# compact.net
KiCad netlist of a schematic drawn in EAGLE
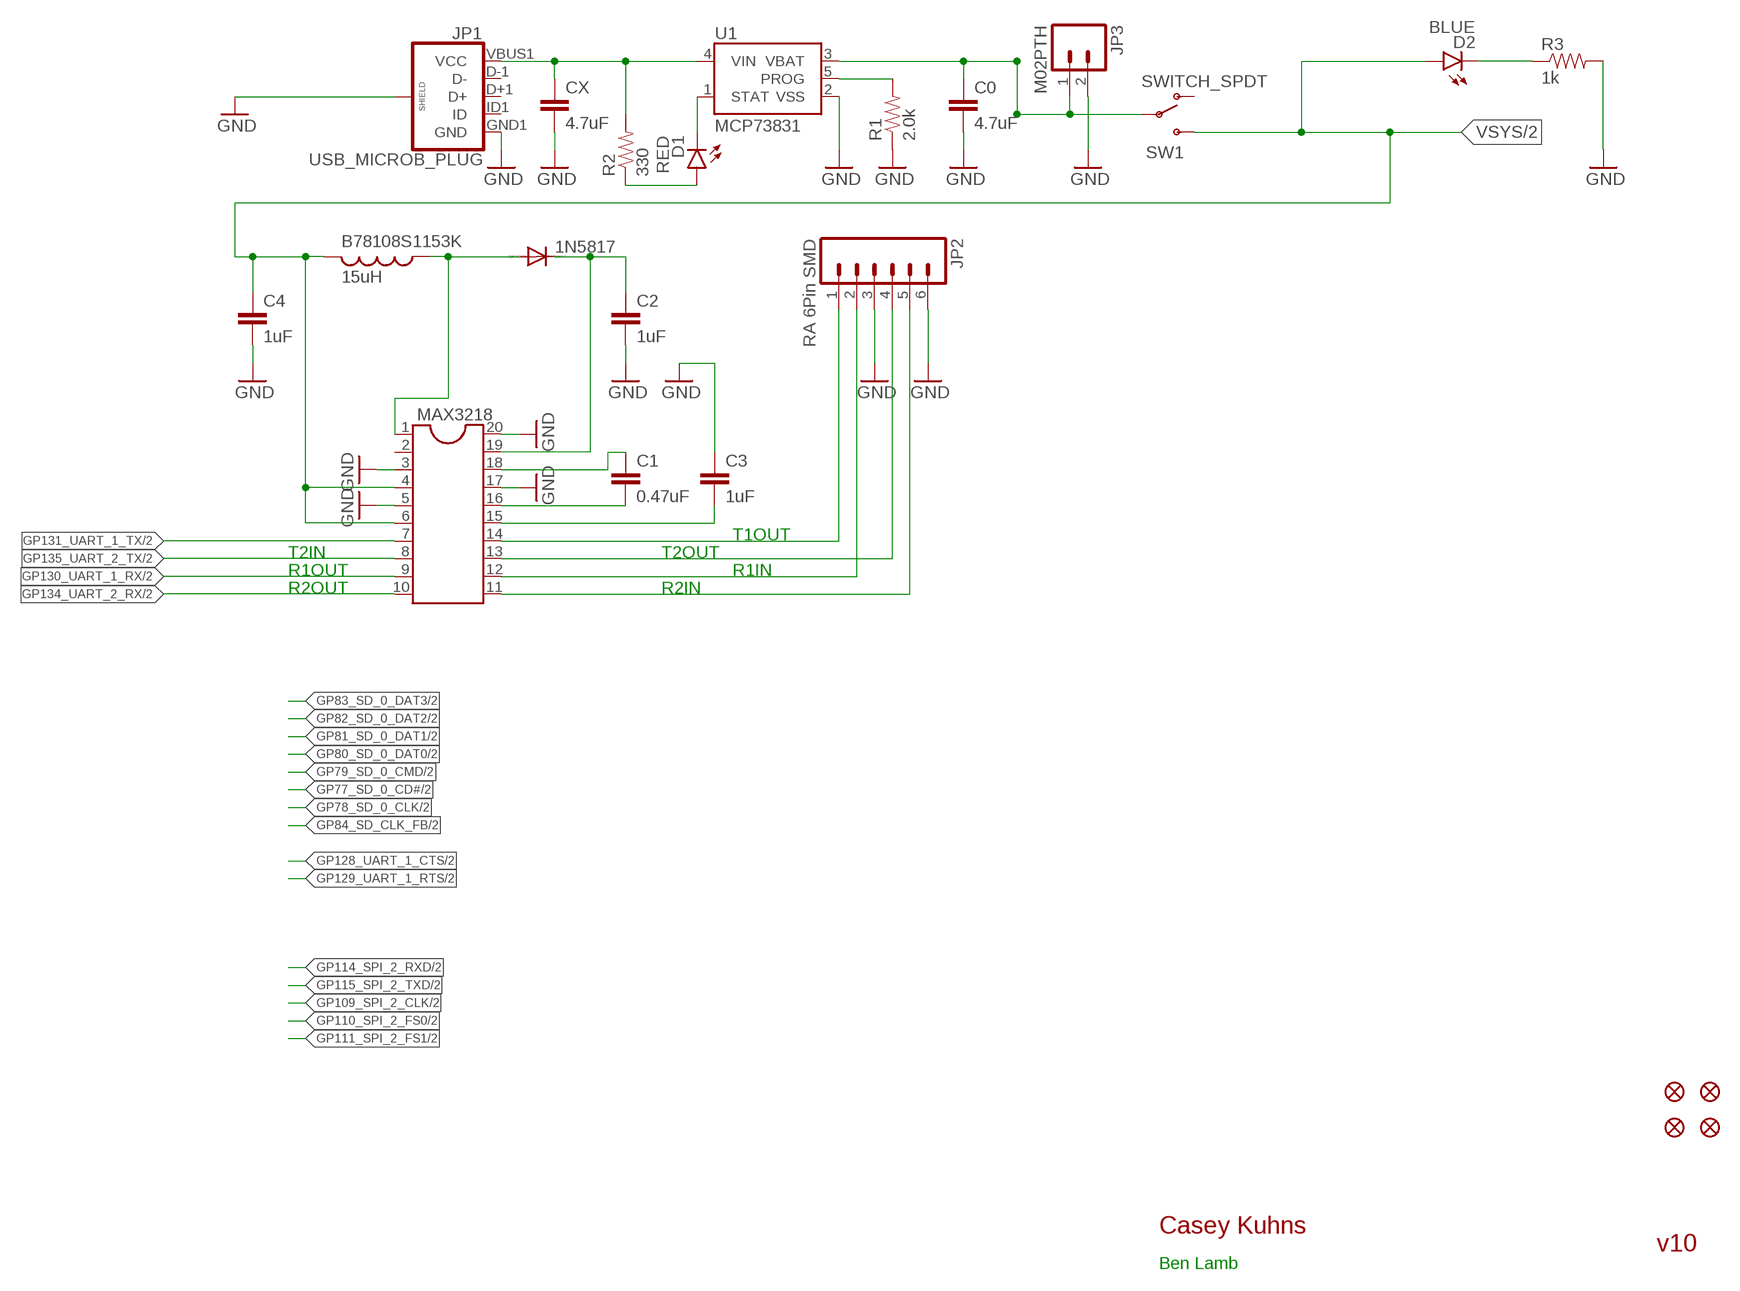
[diagram p0: schematic, sheet 1]
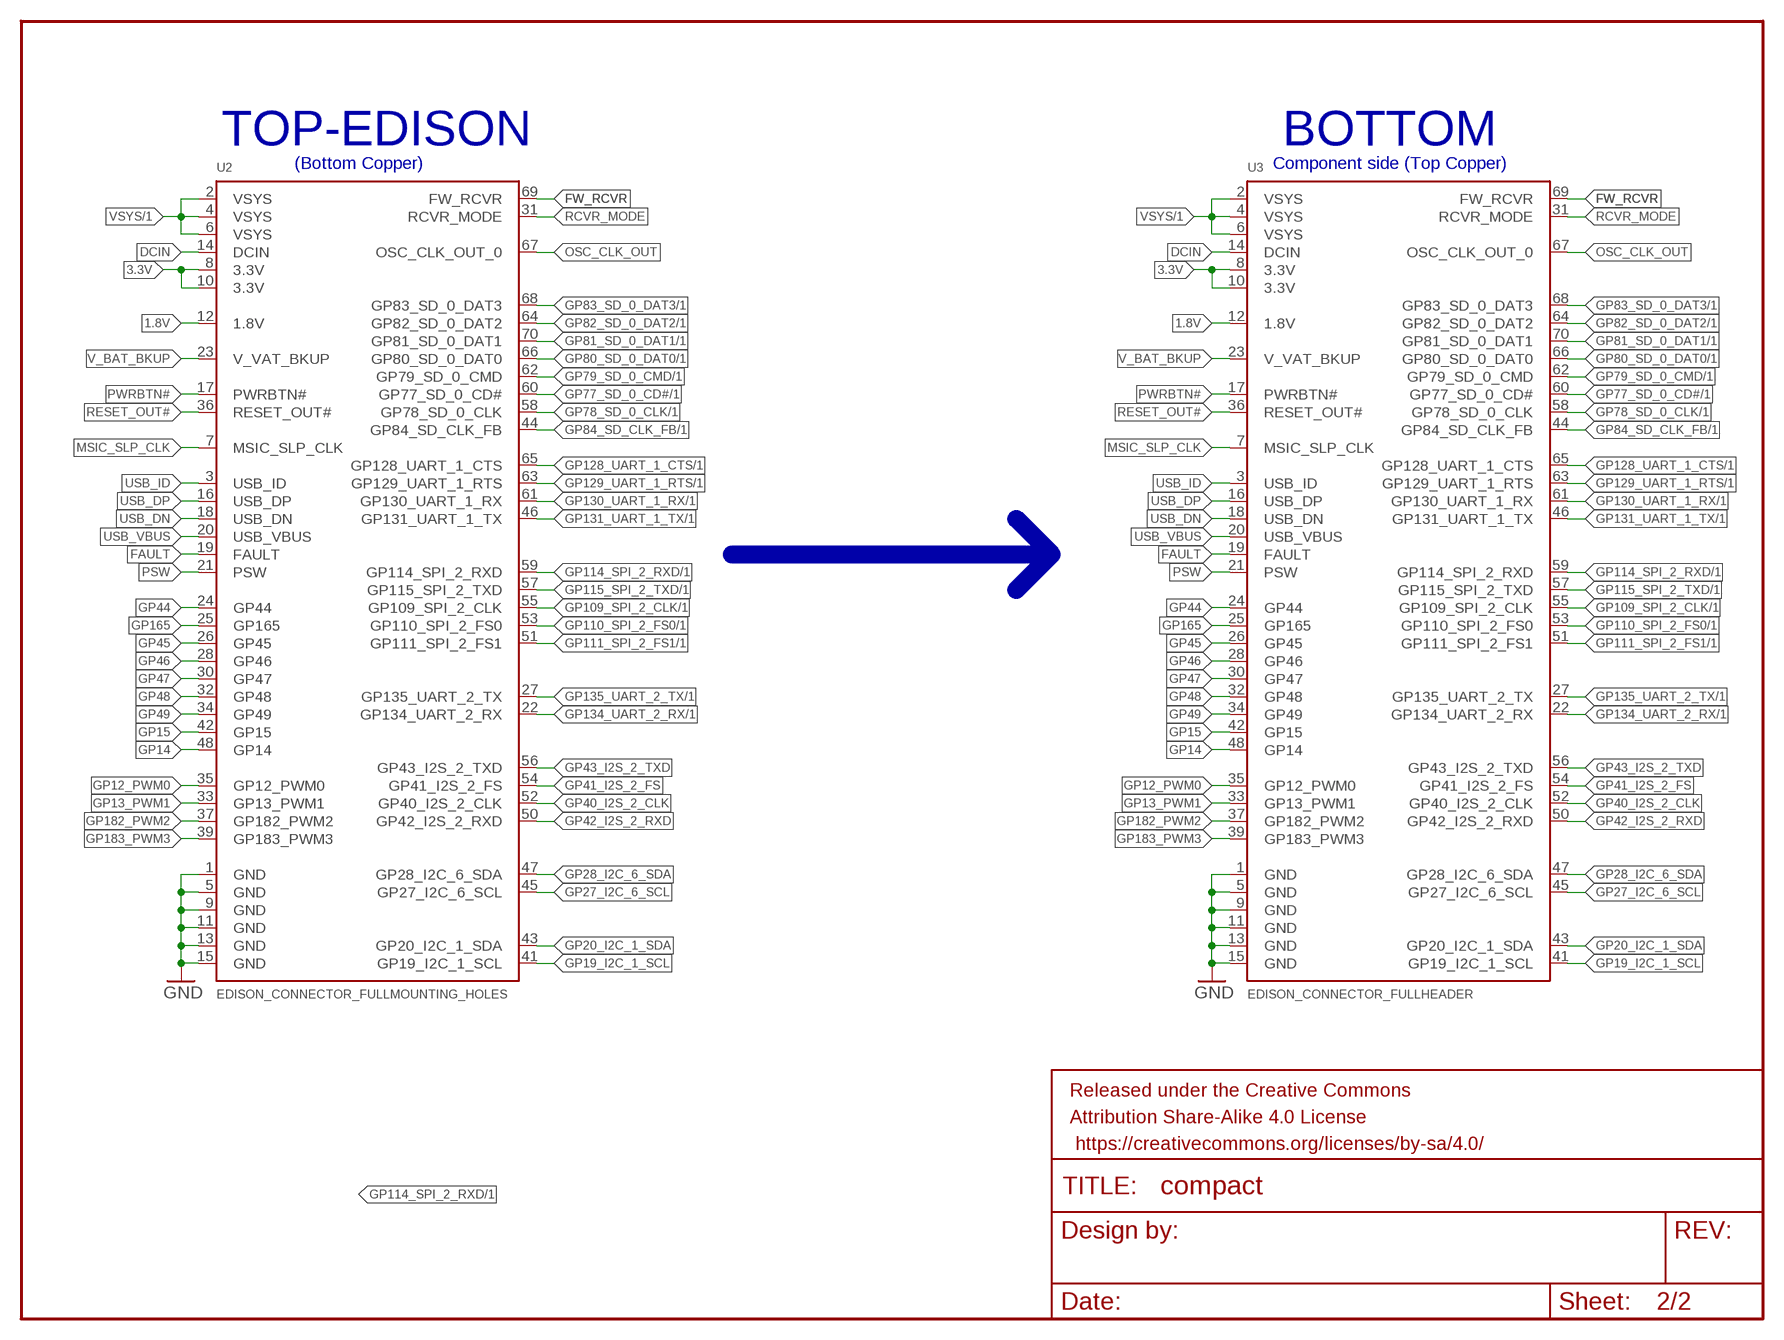
[diagram p1: schematic, sheet 2]

(export (version "E")
  (design (tool "Eeschema 10.0.6"))
  (components
    (comp (ref "FRAME2")
      (value "FRAME-LETTER")
      (footprint "eagle-import:CREATIVE_COMMONS")
      (libsource (lib "eagle-import") (part "FRAME-LETTER"))
    )
    (comp (ref "U2")
      (value "EDISON_CONNECTOR_FULLMOUNTING_HOLES")
      (footprint "eagle-import:EDISON_DAUGHTER")
      (libsource (lib "eagle-import") (part "EDISON_CONNECTOR_FULLMOUNTING_HOLES"))
    )
    (comp (ref "U3")
      (value "EDISON_CONNECTOR_FULLHEADER")
      (footprint "eagle-import:DF40C-70DP-0.4(51)")
      (libsource (lib "eagle-import") (part "EDISON_CONNECTOR_FULLHEADER"))
    )
    (comp (ref "1N5817")
      (value "DIODE-DO41-10")
      (footprint "eagle-import:DO41-10")
      (libsource (lib "eagle-import") (part "DIODE-DO41-10"))
    )
    (comp (ref "B78108S1153K")
      (value "15uH")
      (footprint "eagle-import:0207_15")
      (libsource (lib "eagle-import") (part "L-US0207/15"))
    )
    (comp (ref "C0")
      (value "4.7uF")
      (footprint "eagle-import:0603-CAP")
      (libsource (lib "eagle-import") (part "4.7UF-6.3V-10%(0603)0603"))
    )
    (comp (ref "C1")
      (value "0.47uF")
      (footprint "eagle-import:CAP-PTH-5MM")
      (libsource (lib "eagle-import") (part "CAPPTH1"))
    )
    (comp (ref "C2")
      (value "1uF")
      (footprint "eagle-import:CAP-PTH-5MM")
      (libsource (lib "eagle-import") (part "CAPPTH1"))
    )
    (comp (ref "C3")
      (value "1uF")
      (footprint "eagle-import:CAP-PTH-5MM")
      (libsource (lib "eagle-import") (part "CAPPTH1"))
    )
    (comp (ref "C4")
      (value "1uF")
      (footprint "eagle-import:CAP-PTH-5MM")
      (libsource (lib "eagle-import") (part "CAPPTH1"))
    )
    (comp (ref "CX")
      (value "4.7uF")
      (footprint "eagle-import:0603-CAP")
      (libsource (lib "eagle-import") (part "4.7UF-6.3V-10%(0603)0603"))
    )
    (comp (ref "D1")
      (value "RED")
      (footprint "eagle-import:LED-0603")
      (libsource (lib "eagle-import") (part "LED-RED0603"))
    )
    (comp (ref "D2")
      (value "BLUE")
      (footprint "eagle-import:LED-0603")
      (libsource (lib "eagle-import") (part "LED-BLUE0603"))
    )
    (comp (ref "FID1")
      (value "FIDUCIAL1X2")
      (footprint "eagle-import:FIDUCIAL-1X2")
      (libsource (lib "eagle-import") (part "FIDUCIAL1X2"))
    )
    (comp (ref "FID2")
      (value "FIDUCIAL1X2")
      (footprint "eagle-import:FIDUCIAL-1X2")
      (libsource (lib "eagle-import") (part "FIDUCIAL1X2"))
    )
    (comp (ref "FID3")
      (value "FIDUCIAL1X2")
      (footprint "eagle-import:FIDUCIAL-1X2")
      (libsource (lib "eagle-import") (part "FIDUCIAL1X2"))
    )
    (comp (ref "FID4")
      (value "FIDUCIAL1X2")
      (footprint "eagle-import:FIDUCIAL-1X2")
      (libsource (lib "eagle-import") (part "FIDUCIAL1X2"))
    )
    (comp (ref "JP1")
      (value "USB_MICROB_PLUG")
      (footprint "eagle-import:USB-B-MICRO-SMD_V03")
      (libsource (lib "eagle-import") (part "USB_MICROB_PLUGCONN-11752"))
    )
    (comp (ref "JP2")
      (value "RA 6Pin SMD")
      (footprint "eagle-import:1X06-SMD")
      (libsource (lib "eagle-import") (part "M06SMD"))
    )
    (comp (ref "JP3")
      (value "M02PTH")
      (footprint "eagle-import:1X02")
      (libsource (lib "eagle-import") (part "M02PTH"))
    )
    (comp (ref "MAX3218")
      (value "DIL20")
      (footprint "eagle-import:DIL20")
      (libsource (lib "eagle-import") (part "DIL20"))
    )
    (comp (ref "R1")
      (value "2.0k")
      (footprint "eagle-import:0603-RES")
      (libsource (lib "eagle-import") (part "2.0KOHM1/10W5%(0603)"))
    )
    (comp (ref "R2")
      (value "330")
      (footprint "eagle-import:0603-RES")
      (libsource (lib "eagle-import") (part "330OHM1/10W1%(0603)"))
    )
    (comp (ref "R3")
      (value "1k")
      (footprint "eagle-import:0603-RES")
      (libsource (lib "eagle-import") (part "1KOHM1/10W1%(0603)"))
    )
    (comp (ref "SW1")
      (value "SWITCH_SPDT")
      (footprint "eagle-import:KPS-1290")
      (libsource (lib "eagle-import") (part "SWITCH_SPDT"))
    )
    (comp (ref "U1")
      (value "MCP73831")
      (footprint "eagle-import:SOT23-5")
      (libsource (lib "eagle-import") (part "MCP73831"))
    )
  )
  (nets
    (net (code "1") (name "1.8V") (class "Default")
      (node (ref "U2") (pin "12") (pinfunction "1.8V_12") (pintype "bidirectional"))
      (node (ref "U3") (pin "12") (pinfunction "1.8V_12") (pintype "bidirectional"))
    )
    (net (code "2") (name "3.3V") (class "Default")
      (node (ref "U2") (pin "10") (pinfunction "3.3V_10") (pintype "bidirectional"))
      (node (ref "U2") (pin "8") (pinfunction "3.3V_8") (pintype "bidirectional"))
      (node (ref "U3") (pin "10") (pinfunction "3.3V_10") (pintype "bidirectional"))
      (node (ref "U3") (pin "8") (pinfunction "3.3V_8") (pintype "bidirectional"))
    )
    (net (code "3") (name "DCIN") (class "Default")
      (node (ref "U2") (pin "14") (pinfunction "DCIN_14") (pintype "bidirectional"))
      (node (ref "U3") (pin "14") (pinfunction "DCIN_14") (pintype "bidirectional"))
    )
    (net (code "4") (name "FAULT") (class "Default")
      (node (ref "U2") (pin "19") (pinfunction "FAULT_19") (pintype "bidirectional"))
      (node (ref "U3") (pin "19") (pinfunction "FAULT_19") (pintype "bidirectional"))
    )
    (net (code "5") (name "FW_RCVR") (class "Default")
      (node (ref "U2") (pin "69") (pinfunction "FW_RCVR_69") (pintype "bidirectional"))
      (node (ref "U3") (pin "69") (pinfunction "FW_RCVR_69") (pintype "bidirectional"))
    )
    (net (code "6") (name "GND") (class "Default")
      (node (ref "C0") (pin "2") (pinfunction "2_2") (pintype "passive"))
      (node (ref "C2") (pin "2") (pinfunction "2_2") (pintype "passive"))
      (node (ref "C3") (pin "1") (pinfunction "1_1") (pintype "passive"))
      (node (ref "C4") (pin "2") (pinfunction "2_2") (pintype "passive"))
      (node (ref "CX") (pin "2") (pinfunction "2_2") (pintype "passive"))
      (node (ref "JP1") (pin "GND1") (pinfunction "GND_GND1") (pintype "bidirectional"))
      (node (ref "JP1") (pin "SHIELD1") (pinfunction "SHIELD_SHIELD1") (pintype "bidirectional"))
      (node (ref "JP1") (pin "SHIELD2") (pinfunction "SHIELD_SHIELD2") (pintype "bidirectional"))
      (node (ref "JP1") (pin "SHIELD3") (pinfunction "SHIELD_SHIELD3") (pintype "bidirectional"))
      (node (ref "JP2") (pin "3") (pinfunction "3_3") (pintype "passive"))
      (node (ref "JP2") (pin "6") (pinfunction "6_6") (pintype "passive"))
      (node (ref "JP3") (pin "2") (pinfunction "2_2") (pintype "passive"))
      (node (ref "MAX3218") (pin "17") (pinfunction "17_17") (pintype "passive"))
      (node (ref "MAX3218") (pin "20") (pinfunction "20_20") (pintype "passive"))
      (node (ref "MAX3218") (pin "3") (pinfunction "3_3") (pintype "passive"))
      (node (ref "MAX3218") (pin "5") (pinfunction "5_5") (pintype "passive"))
      (node (ref "R1") (pin "1") (pinfunction "1_1") (pintype "passive"))
      (node (ref "R3") (pin "2") (pinfunction "2_2") (pintype "passive"))
      (node (ref "U1") (pin "2") (pinfunction "VSS_2") (pintype "power_in"))
      (node (ref "U2") (pin "1") (pinfunction "GND_1") (pintype "bidirectional"))
      (node (ref "U2") (pin "11") (pinfunction "GND_11") (pintype "bidirectional"))
      (node (ref "U2") (pin "13") (pinfunction "GND_13") (pintype "bidirectional"))
      (node (ref "U2") (pin "15") (pinfunction "GND_15") (pintype "bidirectional"))
      (node (ref "U2") (pin "5") (pinfunction "GND_5") (pintype "bidirectional"))
      (node (ref "U2") (pin "9") (pinfunction "GND_9") (pintype "bidirectional"))
      (node (ref "U3") (pin "1") (pinfunction "GND_1") (pintype "bidirectional"))
      (node (ref "U3") (pin "11") (pinfunction "GND_11") (pintype "bidirectional"))
      (node (ref "U3") (pin "13") (pinfunction "GND_13") (pintype "bidirectional"))
      (node (ref "U3") (pin "15") (pinfunction "GND_15") (pintype "bidirectional"))
      (node (ref "U3") (pin "5") (pinfunction "GND_5") (pintype "bidirectional"))
      (node (ref "U3") (pin "9") (pinfunction "GND_9") (pintype "bidirectional"))
    )
    (net (code "7") (name "GP12_PWM0") (class "Default")
      (node (ref "U2") (pin "35") (pinfunction "GP12_PWM0_35") (pintype "bidirectional"))
      (node (ref "U3") (pin "35") (pinfunction "GP12_PWM0_35") (pintype "bidirectional"))
    )
    (net (code "8") (name "GP13_PWM1") (class "Default")
      (node (ref "U2") (pin "33") (pinfunction "GP13_PWM1_33") (pintype "bidirectional"))
      (node (ref "U3") (pin "33") (pinfunction "GP13_PWM1_33") (pintype "bidirectional"))
    )
    (net (code "9") (name "GP14") (class "Default")
      (node (ref "U2") (pin "48") (pinfunction "GP14_48") (pintype "bidirectional"))
      (node (ref "U3") (pin "48") (pinfunction "GP14_48") (pintype "bidirectional"))
    )
    (net (code "10") (name "GP15") (class "Default")
      (node (ref "U2") (pin "42") (pinfunction "GP15_42") (pintype "bidirectional"))
      (node (ref "U3") (pin "42") (pinfunction "GP15_42") (pintype "bidirectional"))
    )
    (net (code "11") (name "GP19_I2C_1_SCL") (class "Default")
      (node (ref "U2") (pin "41") (pinfunction "GP19_I2C_1_SCL_41") (pintype "bidirectional"))
      (node (ref "U3") (pin "41") (pinfunction "GP19_I2C_1_SCL_41") (pintype "bidirectional"))
    )
    (net (code "12") (name "GP20_I2C_1_SDA") (class "Default")
      (node (ref "U2") (pin "43") (pinfunction "GP20_I2C_1_SDA_43") (pintype "bidirectional"))
      (node (ref "U3") (pin "43") (pinfunction "GP20_I2C_1_SDA_43") (pintype "bidirectional"))
    )
    (net (code "13") (name "GP27_I2C_6_SCL") (class "Default")
      (node (ref "U2") (pin "45") (pinfunction "GP27_I2C_6_SCL_45") (pintype "bidirectional"))
      (node (ref "U3") (pin "45") (pinfunction "GP27_I2C_6_SCL_45") (pintype "bidirectional"))
    )
    (net (code "14") (name "GP28_I2C_6_SDA") (class "Default")
      (node (ref "U2") (pin "47") (pinfunction "GP28_I2C_6_SDA_47") (pintype "bidirectional"))
      (node (ref "U3") (pin "47") (pinfunction "GP28_I2C_6_SDA_47") (pintype "bidirectional"))
    )
    (net (code "15") (name "GP40_I2S_2_CLK") (class "Default")
      (node (ref "U2") (pin "52") (pinfunction "GP40_I2S_2_CLK_52") (pintype "bidirectional"))
      (node (ref "U3") (pin "52") (pinfunction "GP40_I2S_2_CLK_52") (pintype "bidirectional"))
    )
    (net (code "16") (name "GP41_I2S_2_FS") (class "Default")
      (node (ref "U2") (pin "54") (pinfunction "GP41_I2S_2_FS_54") (pintype "bidirectional"))
      (node (ref "U3") (pin "54") (pinfunction "GP41_I2S_2_FS_54") (pintype "bidirectional"))
    )
    (net (code "17") (name "GP42_I2S_2_RXD") (class "Default")
      (node (ref "U2") (pin "50") (pinfunction "GP42_I2S_2_RXD_50") (pintype "bidirectional"))
      (node (ref "U3") (pin "50") (pinfunction "GP42_I2S_2_RXD_50") (pintype "bidirectional"))
    )
    (net (code "18") (name "GP43_I2S_2_TXD") (class "Default")
      (node (ref "U2") (pin "56") (pinfunction "GP43_I2S_2_TXD_56") (pintype "bidirectional"))
      (node (ref "U3") (pin "56") (pinfunction "GP43_I2S_2_TXD_56") (pintype "bidirectional"))
    )
    (net (code "19") (name "GP44") (class "Default")
      (node (ref "U2") (pin "24") (pinfunction "GP44_24") (pintype "bidirectional"))
      (node (ref "U3") (pin "24") (pinfunction "GP44_24") (pintype "bidirectional"))
    )
    (net (code "20") (name "GP45") (class "Default")
      (node (ref "U2") (pin "26") (pinfunction "GP45_26") (pintype "bidirectional"))
      (node (ref "U3") (pin "26") (pinfunction "GP45_26") (pintype "bidirectional"))
    )
    (net (code "21") (name "GP46") (class "Default")
      (node (ref "U2") (pin "28") (pinfunction "GP46_28") (pintype "bidirectional"))
      (node (ref "U3") (pin "28") (pinfunction "GP46_28") (pintype "bidirectional"))
    )
    (net (code "22") (name "GP47") (class "Default")
      (node (ref "U2") (pin "30") (pinfunction "GP47_30") (pintype "bidirectional"))
      (node (ref "U3") (pin "30") (pinfunction "GP47_30") (pintype "bidirectional"))
    )
    (net (code "23") (name "GP48") (class "Default")
      (node (ref "U2") (pin "32") (pinfunction "GP48_32") (pintype "bidirectional"))
      (node (ref "U3") (pin "32") (pinfunction "GP48_32") (pintype "bidirectional"))
    )
    (net (code "24") (name "GP49") (class "Default")
      (node (ref "U2") (pin "34") (pinfunction "GP49_34") (pintype "bidirectional"))
      (node (ref "U3") (pin "34") (pinfunction "GP49_34") (pintype "bidirectional"))
    )
    (net (code "25") (name "GP77_SD_0_CD#") (class "Default")
      (node (ref "U2") (pin "60") (pinfunction "GP77_SD_0_CD#_60") (pintype "bidirectional"))
      (node (ref "U3") (pin "60") (pinfunction "GP77_SD_0_CD#_60") (pintype "bidirectional"))
    )
    (net (code "26") (name "GP78_SD_0_CLK") (class "Default")
      (node (ref "U2") (pin "58") (pinfunction "GP78_SD_0_CLK_58") (pintype "bidirectional"))
      (node (ref "U3") (pin "58") (pinfunction "GP78_SD_0_CLK_58") (pintype "bidirectional"))
    )
    (net (code "27") (name "GP79_SD_0_CMD") (class "Default")
      (node (ref "U2") (pin "62") (pinfunction "GP79_SD_0_CMD_62") (pintype "bidirectional"))
      (node (ref "U3") (pin "62") (pinfunction "GP79_SD_0_CMD_62") (pintype "bidirectional"))
    )
    (net (code "28") (name "GP80_SD_0_DAT0") (class "Default")
      (node (ref "U2") (pin "66") (pinfunction "GP80_SD_0_DAT0_66") (pintype "bidirectional"))
      (node (ref "U3") (pin "66") (pinfunction "GP80_SD_0_DAT0_66") (pintype "bidirectional"))
    )
    (net (code "29") (name "GP81_SD_0_DAT1") (class "Default")
      (node (ref "U2") (pin "70") (pinfunction "GP81_SD_0_DAT1_70") (pintype "bidirectional"))
      (node (ref "U3") (pin "70") (pinfunction "GP81_SD_0_DAT1_70") (pintype "bidirectional"))
    )
    (net (code "30") (name "GP82_SD_0_DAT2") (class "Default")
      (node (ref "U2") (pin "64") (pinfunction "GP82_SD_0_DAT2_64") (pintype "bidirectional"))
      (node (ref "U3") (pin "64") (pinfunction "GP82_SD_0_DAT2_64") (pintype "bidirectional"))
    )
    (net (code "31") (name "GP83_SD_0_DAT3") (class "Default")
      (node (ref "U2") (pin "68") (pinfunction "GP83_SD_0_DAT3_68") (pintype "bidirectional"))
      (node (ref "U3") (pin "68") (pinfunction "GP83_SD_0_DAT3_68") (pintype "bidirectional"))
    )
    (net (code "32") (name "GP84_SD_CLK_FB") (class "Default")
      (node (ref "U2") (pin "44") (pinfunction "GP84_SD_CLK_FB_44") (pintype "bidirectional"))
      (node (ref "U3") (pin "44") (pinfunction "GP84_SD_CLK_FB_44") (pintype "bidirectional"))
    )
    (net (code "33") (name "GP109_SPI_2_CLK") (class "Default")
      (node (ref "U2") (pin "55") (pinfunction "GP109_SPI_2_CLK_55") (pintype "bidirectional"))
      (node (ref "U3") (pin "55") (pinfunction "GP109_SPI_2_CLK_55") (pintype "bidirectional"))
    )
    (net (code "34") (name "GP110_SPI_2_FS0") (class "Default")
      (node (ref "U2") (pin "53") (pinfunction "GP110_SPI_2_FS0_53") (pintype "bidirectional"))
      (node (ref "U3") (pin "53") (pinfunction "GP110_SPI_2_FS0_53") (pintype "bidirectional"))
    )
    (net (code "35") (name "GP111_SPI_2_FS1") (class "Default")
      (node (ref "U2") (pin "51") (pinfunction "GP111_SPI_2_FS1_51") (pintype "bidirectional"))
      (node (ref "U3") (pin "51") (pinfunction "GP111_SPI_2_FS1_51") (pintype "bidirectional"))
    )
    (net (code "36") (name "GP114_SPI_2_RXD") (class "Default")
      (node (ref "U2") (pin "59") (pinfunction "GP114_SPI_2_RXD_59") (pintype "bidirectional"))
      (node (ref "U3") (pin "59") (pinfunction "GP114_SPI_2_RXD_59") (pintype "bidirectional"))
    )
    (net (code "37") (name "GP115_SPI_2_TXD") (class "Default")
      (node (ref "U2") (pin "57") (pinfunction "GP115_SPI_2_TXD_57") (pintype "bidirectional"))
      (node (ref "U3") (pin "57") (pinfunction "GP115_SPI_2_TXD_57") (pintype "bidirectional"))
    )
    (net (code "38") (name "GP128_UART_1_CTS") (class "Default")
      (node (ref "U2") (pin "65") (pinfunction "GP128_UART_1_CTS_65") (pintype "bidirectional"))
      (node (ref "U3") (pin "65") (pinfunction "GP128_UART_1_CTS_65") (pintype "bidirectional"))
    )
    (net (code "39") (name "GP129_UART_1_RTS") (class "Default")
      (node (ref "U2") (pin "63") (pinfunction "GP129_UART_1_RTS_63") (pintype "bidirectional"))
      (node (ref "U3") (pin "63") (pinfunction "GP129_UART_1_RTS_63") (pintype "bidirectional"))
    )
    (net (code "40") (name "GP130_UART_1_RX") (class "Default")
      (node (ref "MAX3218") (pin "9") (pinfunction "9_9") (pintype "passive"))
      (node (ref "U2") (pin "61") (pinfunction "GP130_UART_1_RX_61") (pintype "bidirectional"))
      (node (ref "U3") (pin "61") (pinfunction "GP130_UART_1_RX_61") (pintype "bidirectional"))
    )
    (net (code "41") (name "GP131_UART_1_TX") (class "Default")
      (node (ref "MAX3218") (pin "7") (pinfunction "7_7") (pintype "passive"))
      (node (ref "U2") (pin "46") (pinfunction "GP131_UART_1_TX_46") (pintype "bidirectional"))
      (node (ref "U3") (pin "46") (pinfunction "GP131_UART_1_TX_46") (pintype "bidirectional"))
    )
    (net (code "42") (name "GP134_UART_2_RX") (class "Default")
      (node (ref "MAX3218") (pin "10") (pinfunction "10_10") (pintype "passive"))
      (node (ref "U2") (pin "22") (pinfunction "GP134_UART_2_RX_22") (pintype "bidirectional"))
      (node (ref "U3") (pin "22") (pinfunction "GP134_UART_2_RX_22") (pintype "bidirectional"))
    )
    (net (code "43") (name "GP135_UART_2_TX") (class "Default")
      (node (ref "MAX3218") (pin "8") (pinfunction "8_8") (pintype "passive"))
      (node (ref "U2") (pin "27") (pinfunction "GP135_UART_2_TX_27") (pintype "bidirectional"))
      (node (ref "U3") (pin "27") (pinfunction "GP135_UART_2_TX_27") (pintype "bidirectional"))
    )
    (net (code "44") (name "GP165") (class "Default")
      (node (ref "U2") (pin "25") (pinfunction "GP165_25") (pintype "bidirectional"))
      (node (ref "U3") (pin "25") (pinfunction "GP165_25") (pintype "bidirectional"))
    )
    (net (code "45") (name "GP182_PWM2") (class "Default")
      (node (ref "U2") (pin "37") (pinfunction "GP182_PWM2_37") (pintype "bidirectional"))
      (node (ref "U3") (pin "37") (pinfunction "GP182_PWM2_37") (pintype "bidirectional"))
    )
    (net (code "46") (name "GP183_PWM3") (class "Default")
      (node (ref "U2") (pin "39") (pinfunction "GP183_PWM3_39") (pintype "bidirectional"))
      (node (ref "U3") (pin "39") (pinfunction "GP183_PWM3_39") (pintype "bidirectional"))
    )
    (net (code "47") (name "MSIC_SLP_CLK") (class "Default")
      (node (ref "U2") (pin "7") (pinfunction "MSIC_SLP_CLK_7") (pintype "bidirectional"))
      (node (ref "U3") (pin "7") (pinfunction "MSIC_SLP_CLK_7") (pintype "bidirectional"))
    )
    (net (code "48") (name "Net-(1N5817-PadA)") (class "Default")
      (node (ref "1N5817") (pin "A") (pinfunction "A_A") (pintype "passive"))
      (node (ref "B78108S1153K") (pin "1") (pinfunction "1_1") (pintype "passive"))
      (node (ref "MAX3218") (pin "1") (pinfunction "1_1") (pintype "passive"))
    )
    (net (code "49") (name "Net-(1N5817-PadC)") (class "Default")
      (node (ref "1N5817") (pin "C") (pinfunction "C_C") (pintype "passive"))
      (node (ref "C2") (pin "1") (pinfunction "1_1") (pintype "passive"))
      (node (ref "MAX3218") (pin "19") (pinfunction "19_19") (pintype "passive"))
    )
    (net (code "50") (name "Net-(C1-Pad1)") (class "Default")
      (node (ref "C1") (pin "1") (pinfunction "1_1") (pintype "passive"))
      (node (ref "MAX3218") (pin "18") (pinfunction "18_18") (pintype "passive"))
    )
    (net (code "51") (name "Net-(C1-Pad2)") (class "Default")
      (node (ref "C1") (pin "2") (pinfunction "2_2") (pintype "passive"))
      (node (ref "MAX3218") (pin "16") (pinfunction "16_16") (pintype "passive"))
    )
    (net (code "52") (name "Net-(C3-Pad2)") (class "Default")
      (node (ref "C3") (pin "2") (pinfunction "2_2") (pintype "passive"))
      (node (ref "MAX3218") (pin "15") (pinfunction "15_15") (pintype "passive"))
    )
    (net (code "53") (name "Net-(D1-PadA)") (class "Default")
      (node (ref "D1") (pin "A") (pinfunction "A_A") (pintype "passive"))
      (node (ref "R2") (pin "1") (pinfunction "1_1") (pintype "passive"))
    )
    (net (code "54") (name "Net-(D2-PadC)") (class "Default")
      (node (ref "D2") (pin "C") (pinfunction "C_C") (pintype "passive"))
      (node (ref "R3") (pin "1") (pinfunction "1_1") (pintype "passive"))
    )
    (net (code "55") (name "Net-(JP1-VCC)") (class "Default")
      (node (ref "CX") (pin "1") (pinfunction "1_1") (pintype "passive"))
      (node (ref "JP1") (pin "VBUS1") (pinfunction "VCC_VBUS1") (pintype "bidirectional"))
      (node (ref "R2") (pin "2") (pinfunction "2_2") (pintype "passive"))
      (node (ref "U1") (pin "4") (pinfunction "VIN_4") (pintype "power_in"))
    )
    (net (code "56") (name "Net-(JP2-Pad1)") (class "Default")
      (node (ref "JP2") (pin "1") (pinfunction "1_1") (pintype "passive"))
      (node (ref "MAX3218") (pin "14") (pinfunction "14_14") (pintype "passive"))
    )
    (net (code "57") (name "Net-(JP2-Pad2)") (class "Default")
      (node (ref "JP2") (pin "2") (pinfunction "2_2") (pintype "passive"))
      (node (ref "MAX3218") (pin "12") (pinfunction "12_12") (pintype "passive"))
    )
    (net (code "58") (name "Net-(JP2-Pad4)") (class "Default")
      (node (ref "JP2") (pin "4") (pinfunction "4_4") (pintype "passive"))
      (node (ref "MAX3218") (pin "13") (pinfunction "13_13") (pintype "passive"))
    )
    (net (code "59") (name "Net-(JP2-Pad5)") (class "Default")
      (node (ref "JP2") (pin "5") (pinfunction "5_5") (pintype "passive"))
      (node (ref "MAX3218") (pin "11") (pinfunction "11_11") (pintype "passive"))
    )
    (net (code "60") (name "Net-(U1-PROG)") (class "Default")
      (node (ref "R1") (pin "2") (pinfunction "2_2") (pintype "passive"))
      (node (ref "U1") (pin "5") (pinfunction "PROG_5") (pintype "input"))
    )
    (net (code "61") (name "Net-(U1-STAT)") (class "Default")
      (node (ref "D1") (pin "C") (pinfunction "C_C") (pintype "passive"))
      (node (ref "U1") (pin "1") (pinfunction "STAT_1") (pintype "output"))
    )
    (net (code "62") (name "Net-(U1-VBAT)") (class "Default")
      (node (ref "C0") (pin "1") (pinfunction "1_1") (pintype "passive"))
      (node (ref "JP3") (pin "1") (pinfunction "1_1") (pintype "passive"))
      (node (ref "SW1") (pin "P") (pinfunction "P_P") (pintype "passive"))
      (node (ref "U1") (pin "3") (pinfunction "VBAT_3") (pintype "power_in"))
    )
    (net (code "63") (name "OSC_CLK_OUT") (class "Default")
      (node (ref "U2") (pin "67") (pinfunction "OSC_CLK_OUT_0_67") (pintype "bidirectional"))
      (node (ref "U3") (pin "67") (pinfunction "OSC_CLK_OUT_0_67") (pintype "bidirectional"))
    )
    (net (code "64") (name "PSW") (class "Default")
      (node (ref "U2") (pin "21") (pinfunction "PSW_21") (pintype "bidirectional"))
      (node (ref "U3") (pin "21") (pinfunction "PSW_21") (pintype "bidirectional"))
    )
    (net (code "65") (name "PWRBTN#") (class "Default")
      (node (ref "U2") (pin "17") (pinfunction "PWRBTN#_17") (pintype "bidirectional"))
      (node (ref "U3") (pin "17") (pinfunction "PWRBTN#_17") (pintype "bidirectional"))
    )
    (net (code "66") (name "RCVR_MODE") (class "Default")
      (node (ref "U2") (pin "31") (pinfunction "RCVR_MODE_31") (pintype "bidirectional"))
      (node (ref "U3") (pin "31") (pinfunction "RCVR_MODE_31") (pintype "bidirectional"))
    )
    (net (code "67") (name "RESET_OUT#") (class "Default")
      (node (ref "U2") (pin "36") (pinfunction "RESET_OUT#_36") (pintype "bidirectional"))
      (node (ref "U3") (pin "36") (pinfunction "RESET_OUT#_36") (pintype "bidirectional"))
    )
    (net (code "68") (name "USB_DN") (class "Default")
      (node (ref "U2") (pin "18") (pinfunction "USB_DN_18") (pintype "bidirectional"))
      (node (ref "U3") (pin "18") (pinfunction "USB_DN_18") (pintype "bidirectional"))
    )
    (net (code "69") (name "USB_DP") (class "Default")
      (node (ref "U2") (pin "16") (pinfunction "USB_DP_16") (pintype "bidirectional"))
      (node (ref "U3") (pin "16") (pinfunction "USB_DP_16") (pintype "bidirectional"))
    )
    (net (code "70") (name "USB_ID") (class "Default")
      (node (ref "U2") (pin "3") (pinfunction "USB_ID_3") (pintype "bidirectional"))
      (node (ref "U3") (pin "3") (pinfunction "USB_ID_3") (pintype "bidirectional"))
    )
    (net (code "71") (name "USB_VBUS") (class "Default")
      (node (ref "U2") (pin "20") (pinfunction "USB_VBUS_20") (pintype "bidirectional"))
      (node (ref "U3") (pin "20") (pinfunction "USB_VBUS_20") (pintype "bidirectional"))
    )
    (net (code "72") (name "VSYS") (class "Default")
      (node (ref "B78108S1153K") (pin "2") (pinfunction "2_2") (pintype "passive"))
      (node (ref "C4") (pin "1") (pinfunction "1_1") (pintype "passive"))
      (node (ref "D2") (pin "A") (pinfunction "A_A") (pintype "passive"))
      (node (ref "MAX3218") (pin "4") (pinfunction "4_4") (pintype "passive"))
      (node (ref "MAX3218") (pin "6") (pinfunction "6_6") (pintype "passive"))
      (node (ref "SW1") (pin "S") (pinfunction "S_S") (pintype "passive"))
      (node (ref "U2") (pin "2") (pinfunction "VSYS_2") (pintype "bidirectional"))
      (node (ref "U2") (pin "4") (pinfunction "VSYS_4") (pintype "bidirectional"))
      (node (ref "U2") (pin "6") (pinfunction "VSYS_6") (pintype "bidirectional"))
      (node (ref "U3") (pin "2") (pinfunction "VSYS_2") (pintype "bidirectional"))
      (node (ref "U3") (pin "4") (pinfunction "VSYS_4") (pintype "bidirectional"))
      (node (ref "U3") (pin "6") (pinfunction "VSYS_6") (pintype "bidirectional"))
    )
    (net (code "73") (name "V_BAT_BKUP") (class "Default")
      (node (ref "U2") (pin "23") (pinfunction "V_VAT_BKUP_23") (pintype "bidirectional"))
      (node (ref "U3") (pin "23") (pinfunction "V_VAT_BKUP_23") (pintype "bidirectional"))
    )
    (net (code "74") (name "unconnected-(JP1-D+-PadD+1)") (class "Default")
      (node (ref "JP1") (pin "D+1") (pinfunction "D+_D+1") (pintype "bidirectional"))
    )
    (net (code "75") (name "unconnected-(JP1-D--PadD-1)") (class "Default")
      (node (ref "JP1") (pin "D-1") (pinfunction "D-_D-1") (pintype "bidirectional"))
    )
    (net (code "76") (name "unconnected-(JP1-ID-PadID1)") (class "Default")
      (node (ref "JP1") (pin "ID1") (pinfunction "ID_ID1") (pintype "bidirectional"))
    )
    (net (code "77") (name "unconnected-(MAX3218-Pad2)") (class "Default")
      (node (ref "MAX3218") (pin "2") (pinfunction "2_2") (pintype "passive"))
    )
    (net (code "78") (name "unconnected-(SW1-PadO)") (class "Default")
      (node (ref "SW1") (pin "O") (pinfunction "O_O") (pintype "passive"))
    )
  )
)
